# Ibrido.net
KiCad netlist of a schematic drawn in EAGLE
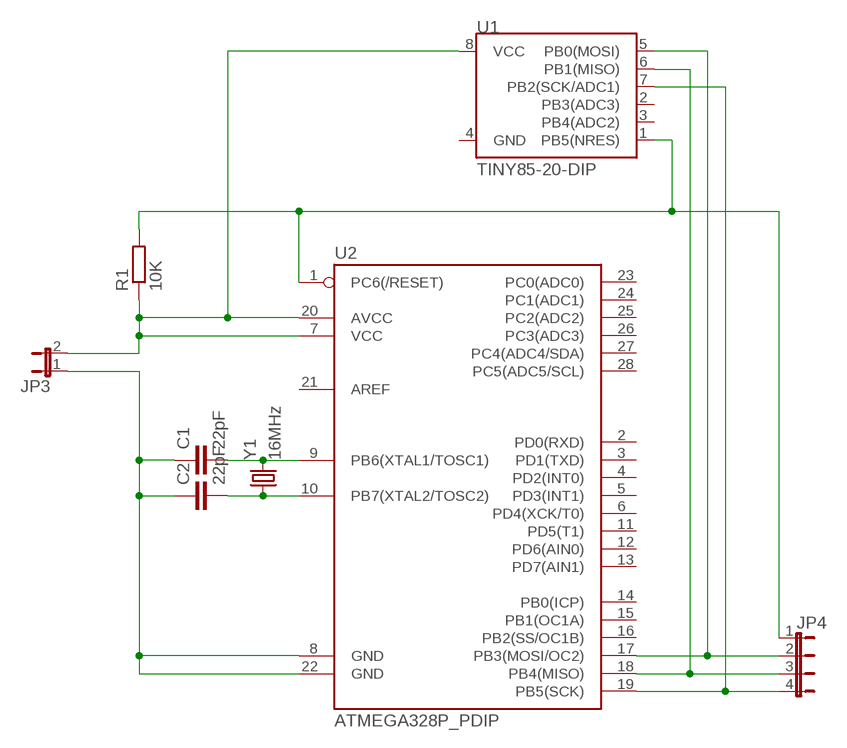
[diagram p0: schematic, sheet 1]

(export (version "E")
  (design (tool "Eeschema 10.0.6"))
  (components
    (comp (ref "C1")
      (value "22pF")
      (footprint "eagle-import:C025-024X044")
      (libsource (lib "eagle-import") (part "C-EU025-024X044"))
    )
    (comp (ref "C2")
      (value "22pF")
      (footprint "eagle-import:C025-024X044")
      (libsource (lib "eagle-import") (part "C-EU025-024X044"))
    )
    (comp (ref "JP3")
      (value "JP1E")
      (footprint "eagle-import:JP1")
      (libsource (lib "eagle-import") (part "JP1E"))
    )
    (comp (ref "JP4")
      (value "JP4E")
      (footprint "eagle-import:JP4")
      (libsource (lib "eagle-import") (part "JP4E"))
    )
    (comp (ref "R1")
      (value "10K")
      (footprint "eagle-import:0207_15")
      (libsource (lib "eagle-import") (part "R-EU_0207/15"))
    )
    (comp (ref "U1")
      (value "TINY85-20-DIP")
      (footprint "eagle-import:DIP08")
      (libsource (lib "eagle-import") (part "ATTINY45TINY85-20-DIP"))
    )
    (comp (ref "U2")
      (value "ATMEGA328P_PDIP")
      (footprint "eagle-import:DIL28-3")
      (libsource (lib "eagle-import") (part "ATMEGA328P_PDIP"))
    )
    (comp (ref "Y1")
      (value "16MHz")
      (footprint "eagle-import:HC49US")
      (libsource (lib "eagle-import") (part "CRYSTALHC49US"))
    )
  )
  (nets
    (net (code "1") (name "Net-(C1-Pad1)") (class "Default")
      (node (ref "C1") (pin "1") (pinfunction "1_1") (pintype "passive"))
      (node (ref "C2") (pin "1") (pinfunction "1_1") (pintype "passive"))
      (node (ref "JP3") (pin "1") (pinfunction "1_1") (pintype "passive"))
      (node (ref "U2") (pin "22") (pinfunction "GND_22") (pintype "bidirectional"))
      (node (ref "U2") (pin "8") (pinfunction "GND_8") (pintype "bidirectional"))
    )
    (net (code "2") (name "Net-(U1-PB0(MOSI))") (class "Default")
      (node (ref "JP4") (pin "2") (pinfunction "2_2") (pintype "passive"))
      (node (ref "U1") (pin "5") (pinfunction "PB0(MOSI)_5") (pintype "bidirectional"))
      (node (ref "U2") (pin "17") (pinfunction "PB3(MOSI/OC2)_17") (pintype "bidirectional"))
    )
    (net (code "3") (name "Net-(U1-PB1(MISO))") (class "Default")
      (node (ref "JP4") (pin "3") (pinfunction "3_3") (pintype "passive"))
      (node (ref "U1") (pin "6") (pinfunction "PB1(MISO)_6") (pintype "bidirectional"))
      (node (ref "U2") (pin "18") (pinfunction "PB4(MISO)_18") (pintype "bidirectional"))
    )
    (net (code "4") (name "Net-(U1-PB2(SCK{slash}ADC1))") (class "Default")
      (node (ref "JP4") (pin "4") (pinfunction "4_4") (pintype "passive"))
      (node (ref "U1") (pin "7") (pinfunction "PB2(SCK/ADC1)_7") (pintype "bidirectional"))
      (node (ref "U2") (pin "19") (pinfunction "PB5(SCK)_19") (pintype "bidirectional"))
    )
    (net (code "5") (name "Net-(U1-PB5(NRES))") (class "Default")
      (node (ref "JP4") (pin "1") (pinfunction "1_1") (pintype "passive"))
      (node (ref "R1") (pin "2") (pinfunction "2_2") (pintype "passive"))
      (node (ref "U1") (pin "1") (pinfunction "PB5(NRES)_1") (pintype "bidirectional"))
      (node (ref "U2") (pin "1") (pinfunction "PC6(/RESET)_1") (pintype "bidirectional"))
    )
    (net (code "6") (name "Net-(U1-VCC)") (class "Default")
      (node (ref "JP3") (pin "2") (pinfunction "2_2") (pintype "passive"))
      (node (ref "R1") (pin "1") (pinfunction "1_1") (pintype "passive"))
      (node (ref "U1") (pin "8") (pinfunction "VCC_8") (pintype "bidirectional"))
      (node (ref "U2") (pin "20") (pinfunction "AVCC_20") (pintype "bidirectional"))
      (node (ref "U2") (pin "7") (pinfunction "VCC_7") (pintype "bidirectional"))
    )
    (net (code "7") (name "Net-(U2-PB6(XTAL1{slash}TOSC1))") (class "Default")
      (node (ref "C1") (pin "2") (pinfunction "2_2") (pintype "passive"))
      (node (ref "U2") (pin "9") (pinfunction "PB6(XTAL1/TOSC1)_9") (pintype "bidirectional"))
      (node (ref "Y1") (pin "2") (pinfunction "2_2") (pintype "passive"))
    )
    (net (code "8") (name "Net-(U2-PB7(XTAL2{slash}TOSC2))") (class "Default")
      (node (ref "C2") (pin "2") (pinfunction "2_2") (pintype "passive"))
      (node (ref "U2") (pin "10") (pinfunction "PB7(XTAL2/TOSC2)_10") (pintype "bidirectional"))
      (node (ref "Y1") (pin "1") (pinfunction "1_1") (pintype "passive"))
    )
    (net (code "9") (name "unconnected-(U1-GND-Pad4)") (class "Default")
      (node (ref "U1") (pin "4") (pinfunction "GND_4") (pintype "bidirectional"))
    )
    (net (code "10") (name "unconnected-(U1-PB3(ADC3)-Pad2)") (class "Default")
      (node (ref "U1") (pin "2") (pinfunction "PB3(ADC3)_2") (pintype "bidirectional"))
    )
    (net (code "11") (name "unconnected-(U1-PB4(ADC2)-Pad3)") (class "Default")
      (node (ref "U1") (pin "3") (pinfunction "PB4(ADC2)_3") (pintype "bidirectional"))
    )
    (net (code "12") (name "unconnected-(U2-AREF-Pad21)") (class "Default")
      (node (ref "U2") (pin "21") (pinfunction "AREF_21") (pintype "bidirectional"))
    )
    (net (code "13") (name "unconnected-(U2-PB0(ICP)-Pad14)") (class "Default")
      (node (ref "U2") (pin "14") (pinfunction "PB0(ICP)_14") (pintype "bidirectional"))
    )
    (net (code "14") (name "unconnected-(U2-PB1(OC1A)-Pad15)") (class "Default")
      (node (ref "U2") (pin "15") (pinfunction "PB1(OC1A)_15") (pintype "bidirectional"))
    )
    (net (code "15") (name "unconnected-(U2-PB2(SS{slash}OC1B)-Pad16)") (class "Default")
      (node (ref "U2") (pin "16") (pinfunction "PB2(SS/OC1B)_16") (pintype "bidirectional"))
    )
    (net (code "16") (name "unconnected-(U2-PC0(ADC0)-Pad23)") (class "Default")
      (node (ref "U2") (pin "23") (pinfunction "PC0(ADC0)_23") (pintype "bidirectional"))
    )
    (net (code "17") (name "unconnected-(U2-PC1(ADC1)-Pad24)") (class "Default")
      (node (ref "U2") (pin "24") (pinfunction "PC1(ADC1)_24") (pintype "bidirectional"))
    )
    (net (code "18") (name "unconnected-(U2-PC2(ADC2)-Pad25)") (class "Default")
      (node (ref "U2") (pin "25") (pinfunction "PC2(ADC2)_25") (pintype "bidirectional"))
    )
    (net (code "19") (name "unconnected-(U2-PC3(ADC3)-Pad26)") (class "Default")
      (node (ref "U2") (pin "26") (pinfunction "PC3(ADC3)_26") (pintype "bidirectional"))
    )
    (net (code "20") (name "unconnected-(U2-PC4(ADC4{slash}SDA)-Pad27)") (class "Default")
      (node (ref "U2") (pin "27") (pinfunction "PC4(ADC4/SDA)_27") (pintype "bidirectional"))
    )
    (net (code "21") (name "unconnected-(U2-PC5(ADC5{slash}SCL)-Pad28)") (class "Default")
      (node (ref "U2") (pin "28") (pinfunction "PC5(ADC5/SCL)_28") (pintype "bidirectional"))
    )
    (net (code "22") (name "unconnected-(U2-PD0(RXD)-Pad2)") (class "Default")
      (node (ref "U2") (pin "2") (pinfunction "PD0(RXD)_2") (pintype "bidirectional"))
    )
    (net (code "23") (name "unconnected-(U2-PD1(TXD)-Pad3)") (class "Default")
      (node (ref "U2") (pin "3") (pinfunction "PD1(TXD)_3") (pintype "bidirectional"))
    )
    (net (code "24") (name "unconnected-(U2-PD2(INT0)-Pad4)") (class "Default")
      (node (ref "U2") (pin "4") (pinfunction "PD2(INT0)_4") (pintype "bidirectional"))
    )
    (net (code "25") (name "unconnected-(U2-PD3(INT1)-Pad5)") (class "Default")
      (node (ref "U2") (pin "5") (pinfunction "PD3(INT1)_5") (pintype "bidirectional"))
    )
    (net (code "26") (name "unconnected-(U2-PD4(XCK{slash}T0)-Pad6)") (class "Default")
      (node (ref "U2") (pin "6") (pinfunction "PD4(XCK/T0)_6") (pintype "bidirectional"))
    )
    (net (code "27") (name "unconnected-(U2-PD5(T1)-Pad11)") (class "Default")
      (node (ref "U2") (pin "11") (pinfunction "PD5(T1)_11") (pintype "bidirectional"))
    )
    (net (code "28") (name "unconnected-(U2-PD6(AIN0)-Pad12)") (class "Default")
      (node (ref "U2") (pin "12") (pinfunction "PD6(AIN0)_12") (pintype "bidirectional"))
    )
    (net (code "29") (name "unconnected-(U2-PD7(AIN1)-Pad13)") (class "Default")
      (node (ref "U2") (pin "13") (pinfunction "PD7(AIN1)_13") (pintype "bidirectional"))
    )
  )
)
